# 12_-_COMMUNICATION.net
KiCad netlist of a schematic drawn in Altium Designer
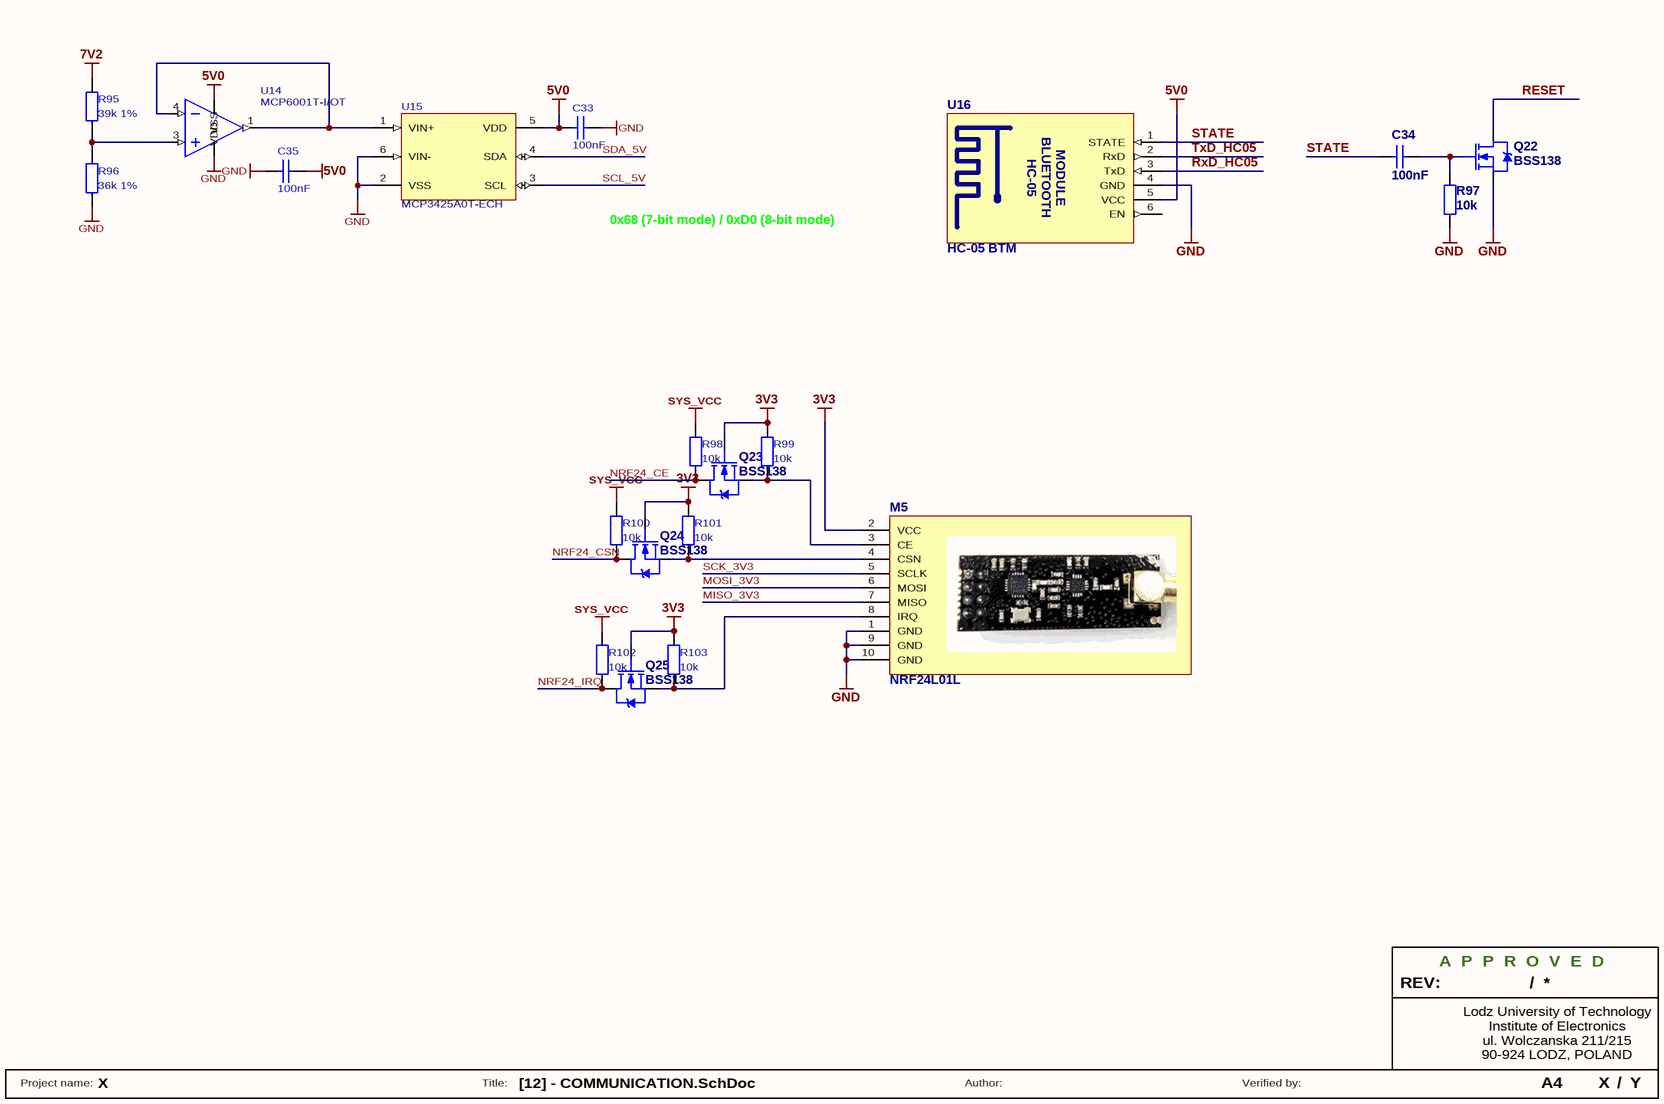
[diagram p0: [12] - COMMUNICATION.SchDoc]

(export (version "E")
  (design (tool "Eeschema 10.0.6"))
  (components
    (comp (ref "C33")
      (value "100nF")
      (footprint "C0805")
      (description "Capacitor")
      (libsource (lib "capacitors") (part "Cap"))
    )
    (comp (ref "C34")
      (value "100nF")
      (footprint "C0805")
      (description "Capacitor")
      (libsource (lib "capacitors") (part "Cap"))
    )
    (comp (ref "C35")
      (value "100nF")
      (footprint "C0805")
      (description "Capacitor")
      (libsource (lib "capacitors") (part "Cap"))
    )
    (comp (ref "M5")
      (value "NRF24L01L")
      (footprint "NRF24L01L")
      (description "Long Range Wireless Module R2 (1.1KM, PA+SMA)")
      (libsource (lib "wireless_modules") (part "NRF24L01L"))
    )
    (comp (ref "Q22")
      (value "BSS138")
      (footprint "SOT-23")
      (description "N-Channel Enhancement Mode Vertical DMOS FET")
      (fields (field (name "PUBLISHER") "Altium Limited"))
      (libsource (lib "transistors_mos") (part "BSS138"))
    )
    (comp (ref "Q23")
      (value "BSS138")
      (footprint "SOT-23")
      (description "N-Channel Enhancement Mode Vertical DMOS FET")
      (fields (field (name "PUBLISHER") "Altium Limited"))
      (libsource (lib "transistors_other") (part "BSS138"))
    )
    (comp (ref "Q24")
      (value "BSS138")
      (footprint "SOT-23")
      (description "N-Channel Enhancement Mode Vertical DMOS FET")
      (fields (field (name "PUBLISHER") "Altium Limited"))
      (libsource (lib "transistors_other") (part "BSS138"))
    )
    (comp (ref "Q25")
      (value "BSS138")
      (footprint "SOT-23")
      (description "N-Channel Enhancement Mode Vertical DMOS FET")
      (fields (field (name "PUBLISHER") "Altium Limited"))
      (libsource (lib "transistors_other") (part "BSS138"))
    )
    (comp (ref "R95")
      (value "39k 1%")
      (footprint "R0805")
      (description "Resistor")
      (libsource (lib "resistors") (part "Res"))
    )
    (comp (ref "R96")
      (value "36k 1%")
      (footprint "R0805")
      (description "Resistor")
      (libsource (lib "resistors") (part "Res"))
    )
    (comp (ref "R97")
      (value "10k")
      (footprint "R0805")
      (description "Resistor")
      (libsource (lib "") (part "Res_1"))
    )
    (comp (ref "R98")
      (value "10k")
      (footprint "R0805")
      (description "Resistor")
      (libsource (lib "resistors") (part "Res"))
    )
    (comp (ref "R99")
      (value "10k")
      (footprint "R0805")
      (description "Resistor")
      (libsource (lib "resistors") (part "Res"))
    )
    (comp (ref "R100")
      (value "10k")
      (footprint "R0805")
      (description "Resistor")
      (libsource (lib "resistors") (part "Res"))
    )
    (comp (ref "R101")
      (value "10k")
      (footprint "R0805")
      (description "Resistor")
      (libsource (lib "resistors") (part "Res"))
    )
    (comp (ref "R102")
      (value "10k")
      (footprint "R0805")
      (description "Resistor")
      (libsource (lib "resistors") (part "Res"))
    )
    (comp (ref "R103")
      (value "10k")
      (footprint "R0805")
      (description "Resistor")
      (libsource (lib "resistors") (part "Res"))
    )
    (comp (ref "U14")
      (value "MCP6001T-I/OT")
      (footprint "SOT-23-5")
      (description "Rail-to-rail, 1MHz, 100uA Op Amp")
      (libsource (lib "opamps") (part "MCP6001T-I/OT"))
    )
    (comp (ref "U15")
      (value "MCP3425A0T-ECH")
      (footprint "SOT-23-6")
      (description "16-Bit Analog-to-Digital Converter with I2C Interface and On-Board Reference")
      (libsource (lib "ad_converters") (part "MCP3425A0T-ECH"))
    )
    (comp (ref "U16")
      (value "HC-05 BTM")
      (footprint "HC-05_H_2")
      (description "HC-05 Bluetooth Module")
      (libsource (lib "wireless_modules") (part "HC-05_BTM"))
    )
  )
  (nets
    (net (code "1") (name "/MISO_3V3") (class "Default")
      (node (ref "M5") (pin "7") (pinfunction "MISO_7") (pintype "passive"))
    )
    (net (code "2") (name "/MOSI_3V3") (class "Default")
      (node (ref "M5") (pin "6") (pinfunction "MOSI_6") (pintype "passive"))
    )
    (net (code "3") (name "/NRF24_CE") (class "Default")
      (node (ref "Q23") (pin "3") (pinfunction "D_3") (pintype "passive"))
      (node (ref "R98") (pin "2") (pinfunction "2_2") (pintype "passive"))
    )
    (net (code "4") (name "/NRF24_CSN") (class "Default")
      (node (ref "Q24") (pin "3") (pinfunction "D_3") (pintype "passive"))
      (node (ref "R100") (pin "2") (pinfunction "2_2") (pintype "passive"))
    )
    (net (code "5") (name "/NRF24_IRQ") (class "Default")
      (node (ref "Q25") (pin "3") (pinfunction "D_3") (pintype "passive"))
      (node (ref "R102") (pin "2") (pinfunction "2_2") (pintype "passive"))
    )
    (net (code "6") (name "/RESET") (class "Default")
      (node (ref "Q22") (pin "3") (pinfunction "D_3") (pintype "passive"))
    )
    (net (code "7") (name "/RxD_HC05") (class "Default")
      (node (ref "U16") (pin "3") (pinfunction "TxD_3") (pintype "input"))
    )
    (net (code "8") (name "/SCK_3V3") (class "Default")
      (node (ref "M5") (pin "5") (pinfunction "SCLK_5") (pintype "passive"))
    )
    (net (code "9") (name "/SCL_5V") (class "Default")
      (node (ref "U15") (pin "3") (pinfunction "SCL_3") (pintype "bidirectional"))
    )
    (net (code "10") (name "/SDA_5V") (class "Default")
      (node (ref "U15") (pin "4") (pinfunction "SDA_4") (pintype "bidirectional"))
    )
    (net (code "11") (name "/STATE") (class "Default")
      (node (ref "C34") (pin "1") (pinfunction "1_1") (pintype "passive"))
      (node (ref "U16") (pin "1") (pinfunction "STATE_1") (pintype "input"))
    )
    (net (code "12") (name "/TxD_HC05") (class "Default")
      (node (ref "U16") (pin "2") (pinfunction "RxD_2") (pintype "output"))
    )
    (net (code "13") (name "3V3") (class "Default")
      (node (ref "M5") (pin "2") (pinfunction "VCC_2") (pintype "passive"))
      (node (ref "Q23") (pin "1") (pinfunction "G_1") (pintype "passive"))
      (node (ref "Q24") (pin "1") (pinfunction "G_1") (pintype "passive"))
      (node (ref "Q25") (pin "1") (pinfunction "G_1") (pintype "passive"))
      (node (ref "R101") (pin "1") (pinfunction "1_1") (pintype "passive"))
      (node (ref "R103") (pin "1") (pinfunction "1_1") (pintype "passive"))
      (node (ref "R99") (pin "1") (pinfunction "1_1") (pintype "passive"))
    )
    (net (code "14") (name "5V0") (class "Default")
      (node (ref "C33") (pin "1") (pinfunction "1_1") (pintype "passive"))
      (node (ref "C35") (pin "1") (pinfunction "1_1") (pintype "passive"))
      (node (ref "U14") (pin "5") (pinfunction "VDD_5") (pintype "power_in"))
      (node (ref "U15") (pin "5") (pinfunction "VDD_5") (pintype "power_in"))
      (node (ref "U16") (pin "5") (pinfunction "VCC_5") (pintype "power_in"))
    )
    (net (code "15") (name "7V2") (class "Default")
      (node (ref "R95") (pin "1") (pinfunction "1_1") (pintype "passive"))
    )
    (net (code "16") (name "GND") (class "Default")
      (node (ref "C33") (pin "2") (pinfunction "2_2") (pintype "passive"))
      (node (ref "C35") (pin "2") (pinfunction "2_2") (pintype "passive"))
      (node (ref "M5") (pin "1") (pinfunction "GND_1") (pintype "passive"))
      (node (ref "M5") (pin "10") (pinfunction "GND_10") (pintype "passive"))
      (node (ref "M5") (pin "9") (pinfunction "GND_9") (pintype "passive"))
      (node (ref "Q22") (pin "2") (pinfunction "S_2") (pintype "passive"))
      (node (ref "R96") (pin "2") (pinfunction "2_2") (pintype "passive"))
      (node (ref "R97") (pin "2") (pinfunction "2_2") (pintype "passive"))
      (node (ref "U14") (pin "2") (pinfunction "VSS_2") (pintype "power_in"))
      (node (ref "U15") (pin "2") (pinfunction "VSS_2") (pintype "power_in"))
      (node (ref "U15") (pin "6") (pinfunction "VIN-_6") (pintype "input"))
      (node (ref "U16") (pin "4") (pinfunction "GND_4") (pintype "power_in"))
    )
    (net (code "17") (name "Net-(M5-CE)") (class "Default")
      (node (ref "M5") (pin "3") (pinfunction "CE_3") (pintype "passive"))
      (node (ref "Q23") (pin "2") (pinfunction "S_2") (pintype "passive"))
      (node (ref "R99") (pin "2") (pinfunction "2_2") (pintype "passive"))
    )
    (net (code "18") (name "Net-(M5-CSN)") (class "Default")
      (node (ref "M5") (pin "4") (pinfunction "CSN_4") (pintype "passive"))
      (node (ref "Q24") (pin "2") (pinfunction "S_2") (pintype "passive"))
      (node (ref "R101") (pin "2") (pinfunction "2_2") (pintype "passive"))
    )
    (net (code "19") (name "Net-(M5-IRQ)") (class "Default")
      (node (ref "M5") (pin "8") (pinfunction "IRQ_8") (pintype "passive"))
      (node (ref "Q25") (pin "2") (pinfunction "S_2") (pintype "passive"))
      (node (ref "R103") (pin "2") (pinfunction "2_2") (pintype "passive"))
    )
    (net (code "20") (name "Net-(Q22-G)") (class "Default")
      (node (ref "C34") (pin "2") (pinfunction "2_2") (pintype "passive"))
      (node (ref "Q22") (pin "1") (pinfunction "G_1") (pintype "passive"))
      (node (ref "R97") (pin "1") (pinfunction "1_1") (pintype "passive"))
    )
    (net (code "21") (name "Net-(U14-IN+)") (class "Default")
      (node (ref "R95") (pin "2") (pinfunction "2_2") (pintype "passive"))
      (node (ref "R96") (pin "1") (pinfunction "1_1") (pintype "passive"))
      (node (ref "U14") (pin "3") (pinfunction "IN+_3") (pintype "input"))
    )
    (net (code "22") (name "Net-(U14-IN-)") (class "Default")
      (node (ref "U14") (pin "1") (pinfunction "OUT_1") (pintype "output"))
      (node (ref "U14") (pin "4") (pinfunction "IN-_4") (pintype "input"))
      (node (ref "U15") (pin "1") (pinfunction "VIN+_1") (pintype "input"))
    )
    (net (code "23") (name "SYS_VCC") (class "Default")
      (node (ref "R100") (pin "1") (pinfunction "1_1") (pintype "passive"))
      (node (ref "R102") (pin "1") (pinfunction "1_1") (pintype "passive"))
      (node (ref "R98") (pin "1") (pinfunction "1_1") (pintype "passive"))
    )
    (net (code "24") (name "unconnected-(U16-EN-Pad6)") (class "Default")
      (node (ref "U16") (pin "6") (pinfunction "EN_6") (pintype "output"))
    )
  )
)
